# HIVE_BOARD_MISC.net
KiCad netlist of a schematic drawn in Altium Designer
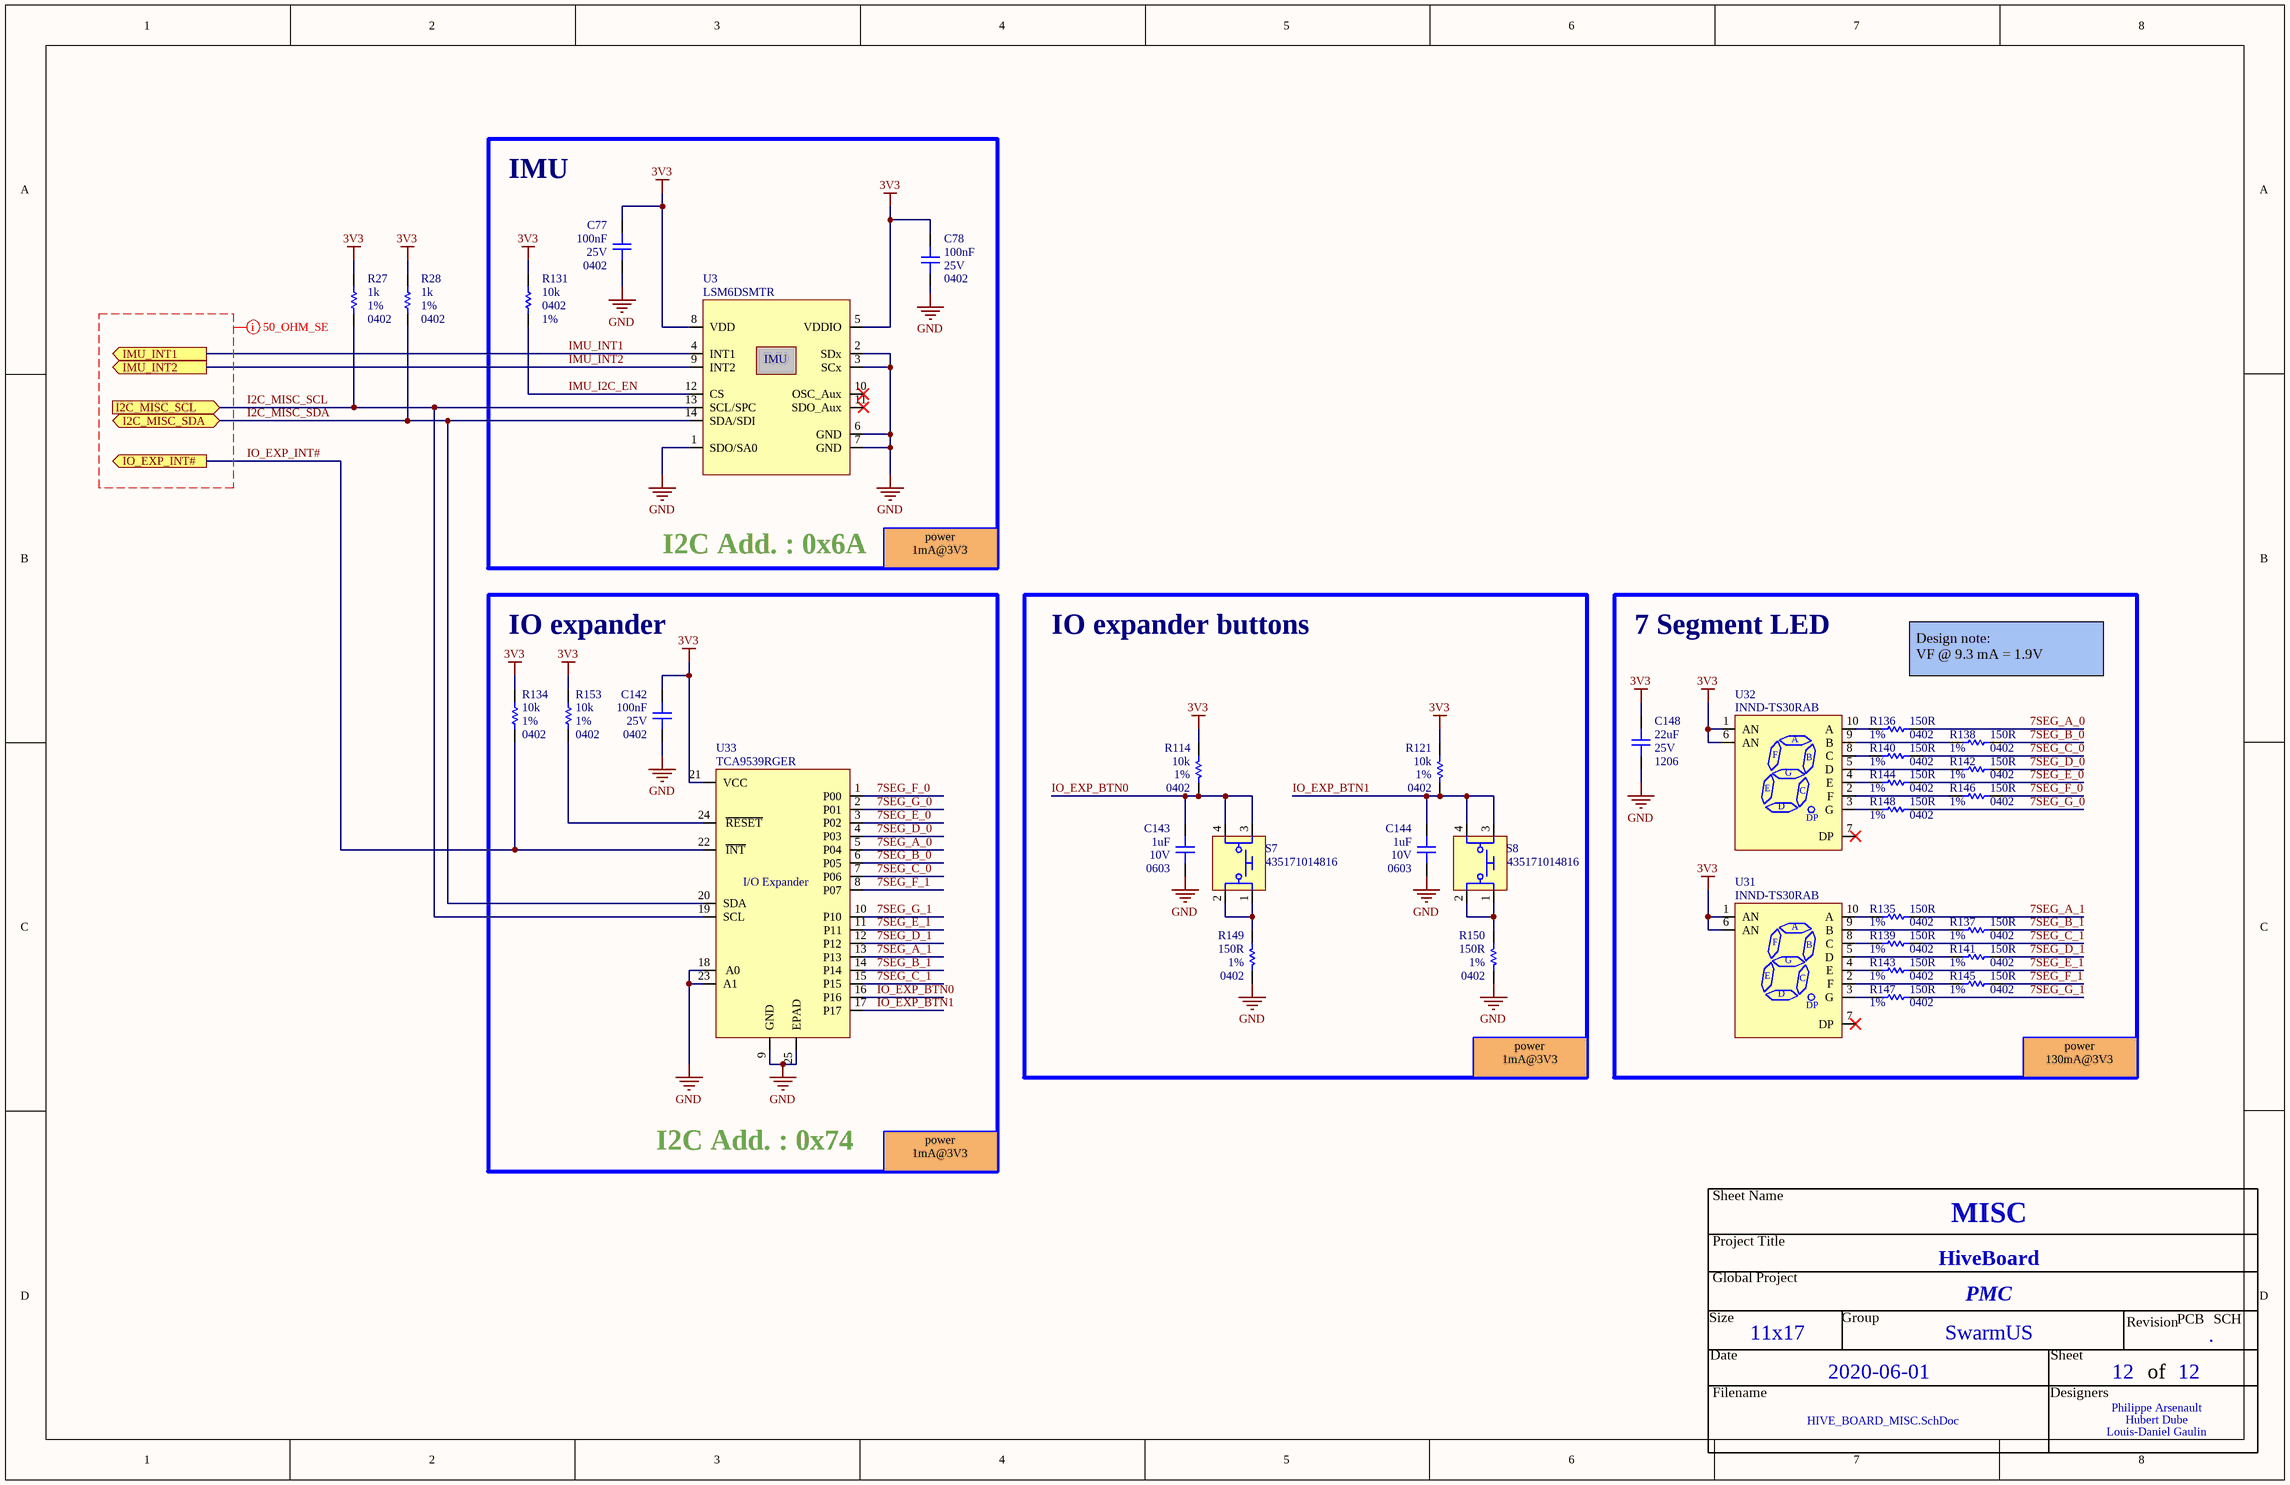
[diagram p0: HIVE_BOARD_MISC.SchDoc]

(export (version "E")
  (design (tool "Eeschema 10.0.6"))
  (components
    (comp (ref "C77")
      (value "100nF")
      (footprint "CAP_CER_0402")
      (description "CAP - CER 0.1µF 10% 25V X7R - 0402")
      (fields
        (field (name "TOLERANCE") "10%")
        (field (name "PACKAGE") "0402")
        (field (name "VOLTAGE RATING") "25V")
        (field (name "Comment") "CGA2B3X7R1E104K050BB")
        (field (name "CREATEDBY/DATE") "Nicolas Roy 2018-11-07")
        (field (name "VERIFIEDBY") "Nicolas V. (2019-01-22)")
      )
      (libsource (lib "GRAMS_MASTER_LIB") (part "CAP_CER_CGA2B3X7R1E104K050BB"))
    )
    (comp (ref "C78")
      (value "100nF")
      (footprint "CAP_CER_0402")
      (description "CAP - CER 0.1µF 10% 25V X7R - 0402")
      (fields
        (field (name "TOLERANCE") "10%")
        (field (name "PACKAGE") "0402")
        (field (name "VOLTAGE RATING") "25V")
        (field (name "Comment") "CGA2B3X7R1E104K050BB")
        (field (name "CREATEDBY/DATE") "Nicolas Roy 2018-11-07")
        (field (name "VERIFIEDBY") "Nicolas V. (2019-01-22)")
      )
      (libsource (lib "GRAMS_MASTER_LIB") (part "CAP_CER_CGA2B3X7R1E104K050BB"))
    )
    (comp (ref "C142")
      (value "100nF")
      (footprint "CAP_CER_0402")
      (description "CAP - CER 0.1µF 10% 25V X7R - 0402")
      (fields
        (field (name "TOLERANCE") "10%")
        (field (name "PACKAGE") "0402")
        (field (name "VOLTAGE RATING") "25V")
        (field (name "Comment") "CGA2B3X7R1E104K050BB")
        (field (name "CREATEDBY/DATE") "Nicolas Roy 2018-11-07")
        (field (name "VERIFIEDBY") "Nicolas V. (2019-01-22)")
      )
      (libsource (lib "GRAMS_MASTER_LIB") (part "CAP_CER_CGA2B3X7R1E104K050BB"))
    )
    (comp (ref "C143")
      (value "1uF")
      (footprint "CAP_CER_0603")
      (description "CAP - CER 1uF 10V 10% X5R - 0603")
      (fields
        (field (name "TOLERANCE") "10%")
        (field (name "PACKAGE") "0603")
        (field (name "VOLTAGE RATING") "10V")
        (field (name "Comment") "C0603C105K8PACTU")
        (field (name "CREATEDBY/DATE") "Hubert Dube - 21/07/20")
        (field (name "VERIFIEDBY") "Louis-Daniel Gaulin - 21/07/20")
      )
      (libsource (lib "SWARMUS_LIB") (part "CAP_CER_C0603C105K8PACTU"))
    )
    (comp (ref "C144")
      (value "1uF")
      (footprint "CAP_CER_0603")
      (description "CAP - CER 1uF 10V 10% X5R - 0603")
      (fields
        (field (name "TOLERANCE") "10%")
        (field (name "PACKAGE") "0603")
        (field (name "VOLTAGE RATING") "10V")
        (field (name "Comment") "C0603C105K8PACTU")
        (field (name "CREATEDBY/DATE") "Hubert Dube - 21/07/20")
        (field (name "VERIFIEDBY") "Louis-Daniel Gaulin - 21/07/20")
      )
      (libsource (lib "SWARMUS_LIB") (part "CAP_CER_C0603C105K8PACTU"))
    )
    (comp (ref "C148")
      (value "22uF")
      (footprint "CAP_CER_1206")
      (description "CAP - CER 22uF 10% 25V X5R - 1206")
      (fields
        (field (name "TOLERANCE") "10%")
        (field (name "PACKAGE") "1206")
        (field (name "VOLTAGE RATING") "25V")
        (field (name "Comment") "CL31A226KAHNNNE")
        (field (name "CREATEDBY/DATE") "Philippe Arsenault/21 Janvier 2020")
        (field (name "VERIFIEDBY") "C.Paulin - 28/01/2020")
      )
      (libsource (lib "GRAMS_MASTER_LIB") (part "CAP_CER_CL31A226KAHNNNE"))
    )
    (comp (ref "R27")
      (value "1k")
      (footprint "RES_0402")
      (description "RES - 1K OHM 1% 1/16W - 0402")
      (fields
        (field (name "TOLERANCE") "1%")
        (field (name "PACKAGE") "0402")
        (field (name "Comment") "RC0402FR-071KL")
        (field (name "CREATEDBY/DATE") "Jonathan Bouchard 2018-07-05")
        (field (name "VERIFIEDBY") "Arnaud Samson 16-07-18")
      )
      (libsource (lib "GRAMS_MASTER_LIB") (part "RES_RC0402FR-071KL"))
    )
    (comp (ref "R28")
      (value "1k")
      (footprint "RES_0402")
      (description "RES - 1K OHM 1% 1/16W - 0402")
      (fields
        (field (name "TOLERANCE") "1%")
        (field (name "PACKAGE") "0402")
        (field (name "Comment") "RC0402FR-071KL")
        (field (name "CREATEDBY/DATE") "Jonathan Bouchard 2018-07-05")
        (field (name "VERIFIEDBY") "Arnaud Samson 16-07-18")
      )
      (libsource (lib "GRAMS_MASTER_LIB") (part "RES_RC0402FR-071KL"))
    )
    (comp (ref "R114")
      (value "10k")
      (footprint "RES_0402")
      (description "RES - 10K OHMS 1% 1/16W - 0402")
      (fields
        (field (name "TOLERANCE") "1%")
        (field (name "PACKAGE") "0402")
        (field (name "Comment") "RC0402FR-0710KL")
        (field (name "CREATEDBY/DATE") "Nicolas V. (2018-11-20)")
        (field (name "VERIFIEDBY") "Nicolas V. (2018-11-20)")
      )
      (libsource (lib "GRAMS_MASTER_LIB") (part "RES_RC0402FR-0710KL"))
    )
    (comp (ref "R121")
      (value "10k")
      (footprint "RES_0402")
      (description "RES - 10K OHMS 1% 1/16W - 0402")
      (fields
        (field (name "TOLERANCE") "1%")
        (field (name "PACKAGE") "0402")
        (field (name "Comment") "RC0402FR-0710KL")
        (field (name "CREATEDBY/DATE") "Nicolas V. (2018-11-20)")
        (field (name "VERIFIEDBY") "Nicolas V. (2018-11-20)")
      )
      (libsource (lib "GRAMS_MASTER_LIB") (part "RES_RC0402FR-0710KL"))
    )
    (comp (ref "R131")
      (value "10k")
      (footprint "RES_0402")
      (description "RES - 10K OHMS 1% 1/16W - 0402")
      (fields
        (field (name "TOLERANCE") "1%")
        (field (name "PACKAGE") "0402")
        (field (name "Comment") "RC0402FR-0710KL")
        (field (name "CREATEDBY/DATE") "Nicolas V. (2018-11-20)")
        (field (name "VERIFIEDBY") "Nicolas V. (2018-11-20)")
      )
      (libsource (lib "GRAMS_MASTER_LIB") (part "RES_RC0402FR-0710KL"))
    )
    (comp (ref "R134")
      (value "10k")
      (footprint "RES_0402")
      (description "RES - 10K OHMS 1% 1/16W - 0402")
      (fields
        (field (name "TOLERANCE") "1%")
        (field (name "PACKAGE") "0402")
        (field (name "Comment") "RC0402FR-0710KL")
        (field (name "CREATEDBY/DATE") "Nicolas V. (2018-11-20)")
        (field (name "VERIFIEDBY") "Nicolas V. (2018-11-20)")
      )
      (libsource (lib "GRAMS_MASTER_LIB") (part "RES_RC0402FR-0710KL"))
    )
    (comp (ref "R135")
      (value "150R")
      (footprint "RES_0402")
      (description "RES - 150R 1% 1/16W - 0402")
      (fields
        (field (name "TOLERANCE") "1%")
        (field (name "PACKAGE") "0402")
        (field (name "Comment") "RC0402FR-07150RL")
        (field (name "CREATEDBY/DATE") "Jonathan Bouchard 2019-03-25")
        (field (name "VERIFIEDBY") "Nicolas V. (2019-05-02)")
      )
      (libsource (lib "GRAMS_MASTER_LIB") (part "RES_RC0402FR-07150RL"))
    )
    (comp (ref "R136")
      (value "150R")
      (footprint "RES_0402")
      (description "RES - 150R 1% 1/16W - 0402")
      (fields
        (field (name "TOLERANCE") "1%")
        (field (name "PACKAGE") "0402")
        (field (name "Comment") "RC0402FR-07150RL")
        (field (name "CREATEDBY/DATE") "Jonathan Bouchard 2019-03-25")
        (field (name "VERIFIEDBY") "Nicolas V. (2019-05-02)")
      )
      (libsource (lib "GRAMS_MASTER_LIB") (part "RES_RC0402FR-07150RL"))
    )
    (comp (ref "R137")
      (value "150R")
      (footprint "RES_0402")
      (description "RES - 150R 1% 1/16W - 0402")
      (fields
        (field (name "TOLERANCE") "1%")
        (field (name "PACKAGE") "0402")
        (field (name "Comment") "RC0402FR-07150RL")
        (field (name "CREATEDBY/DATE") "Jonathan Bouchard 2019-03-25")
        (field (name "VERIFIEDBY") "Nicolas V. (2019-05-02)")
      )
      (libsource (lib "GRAMS_MASTER_LIB") (part "RES_RC0402FR-07150RL"))
    )
    (comp (ref "R138")
      (value "150R")
      (footprint "RES_0402")
      (description "RES - 150R 1% 1/16W - 0402")
      (fields
        (field (name "TOLERANCE") "1%")
        (field (name "PACKAGE") "0402")
        (field (name "Comment") "RC0402FR-07150RL")
        (field (name "CREATEDBY/DATE") "Jonathan Bouchard 2019-03-25")
        (field (name "VERIFIEDBY") "Nicolas V. (2019-05-02)")
      )
      (libsource (lib "GRAMS_MASTER_LIB") (part "RES_RC0402FR-07150RL"))
    )
    (comp (ref "R139")
      (value "150R")
      (footprint "RES_0402")
      (description "RES - 150R 1% 1/16W - 0402")
      (fields
        (field (name "TOLERANCE") "1%")
        (field (name "PACKAGE") "0402")
        (field (name "Comment") "RC0402FR-07150RL")
        (field (name "CREATEDBY/DATE") "Jonathan Bouchard 2019-03-25")
        (field (name "VERIFIEDBY") "Nicolas V. (2019-05-02)")
      )
      (libsource (lib "GRAMS_MASTER_LIB") (part "RES_RC0402FR-07150RL"))
    )
    (comp (ref "R140")
      (value "150R")
      (footprint "RES_0402")
      (description "RES - 150R 1% 1/16W - 0402")
      (fields
        (field (name "TOLERANCE") "1%")
        (field (name "PACKAGE") "0402")
        (field (name "Comment") "RC0402FR-07150RL")
        (field (name "CREATEDBY/DATE") "Jonathan Bouchard 2019-03-25")
        (field (name "VERIFIEDBY") "Nicolas V. (2019-05-02)")
      )
      (libsource (lib "GRAMS_MASTER_LIB") (part "RES_RC0402FR-07150RL"))
    )
    (comp (ref "R141")
      (value "150R")
      (footprint "RES_0402")
      (description "RES - 150R 1% 1/16W - 0402")
      (fields
        (field (name "TOLERANCE") "1%")
        (field (name "PACKAGE") "0402")
        (field (name "Comment") "RC0402FR-07150RL")
        (field (name "CREATEDBY/DATE") "Jonathan Bouchard 2019-03-25")
        (field (name "VERIFIEDBY") "Nicolas V. (2019-05-02)")
      )
      (libsource (lib "GRAMS_MASTER_LIB") (part "RES_RC0402FR-07150RL"))
    )
    (comp (ref "R142")
      (value "150R")
      (footprint "RES_0402")
      (description "RES - 150R 1% 1/16W - 0402")
      (fields
        (field (name "TOLERANCE") "1%")
        (field (name "PACKAGE") "0402")
        (field (name "Comment") "RC0402FR-07150RL")
        (field (name "CREATEDBY/DATE") "Jonathan Bouchard 2019-03-25")
        (field (name "VERIFIEDBY") "Nicolas V. (2019-05-02)")
      )
      (libsource (lib "GRAMS_MASTER_LIB") (part "RES_RC0402FR-07150RL"))
    )
    (comp (ref "R143")
      (value "150R")
      (footprint "RES_0402")
      (description "RES - 150R 1% 1/16W - 0402")
      (fields
        (field (name "TOLERANCE") "1%")
        (field (name "PACKAGE") "0402")
        (field (name "Comment") "RC0402FR-07150RL")
        (field (name "CREATEDBY/DATE") "Jonathan Bouchard 2019-03-25")
        (field (name "VERIFIEDBY") "Nicolas V. (2019-05-02)")
      )
      (libsource (lib "GRAMS_MASTER_LIB") (part "RES_RC0402FR-07150RL"))
    )
    (comp (ref "R144")
      (value "150R")
      (footprint "RES_0402")
      (description "RES - 150R 1% 1/16W - 0402")
      (fields
        (field (name "TOLERANCE") "1%")
        (field (name "PACKAGE") "0402")
        (field (name "Comment") "RC0402FR-07150RL")
        (field (name "CREATEDBY/DATE") "Jonathan Bouchard 2019-03-25")
        (field (name "VERIFIEDBY") "Nicolas V. (2019-05-02)")
      )
      (libsource (lib "GRAMS_MASTER_LIB") (part "RES_RC0402FR-07150RL"))
    )
    (comp (ref "R145")
      (value "150R")
      (footprint "RES_0402")
      (description "RES - 150R 1% 1/16W - 0402")
      (fields
        (field (name "TOLERANCE") "1%")
        (field (name "PACKAGE") "0402")
        (field (name "Comment") "RC0402FR-07150RL")
        (field (name "CREATEDBY/DATE") "Jonathan Bouchard 2019-03-25")
        (field (name "VERIFIEDBY") "Nicolas V. (2019-05-02)")
      )
      (libsource (lib "GRAMS_MASTER_LIB") (part "RES_RC0402FR-07150RL"))
    )
    (comp (ref "R146")
      (value "150R")
      (footprint "RES_0402")
      (description "RES - 150R 1% 1/16W - 0402")
      (fields
        (field (name "TOLERANCE") "1%")
        (field (name "PACKAGE") "0402")
        (field (name "Comment") "RC0402FR-07150RL")
        (field (name "CREATEDBY/DATE") "Jonathan Bouchard 2019-03-25")
        (field (name "VERIFIEDBY") "Nicolas V. (2019-05-02)")
      )
      (libsource (lib "GRAMS_MASTER_LIB") (part "RES_RC0402FR-07150RL"))
    )
    (comp (ref "R147")
      (value "150R")
      (footprint "RES_0402")
      (description "RES - 150R 1% 1/16W - 0402")
      (fields
        (field (name "TOLERANCE") "1%")
        (field (name "PACKAGE") "0402")
        (field (name "Comment") "RC0402FR-07150RL")
        (field (name "CREATEDBY/DATE") "Jonathan Bouchard 2019-03-25")
        (field (name "VERIFIEDBY") "Nicolas V. (2019-05-02)")
      )
      (libsource (lib "GRAMS_MASTER_LIB") (part "RES_RC0402FR-07150RL"))
    )
    (comp (ref "R148")
      (value "150R")
      (footprint "RES_0402")
      (description "RES - 150R 1% 1/16W - 0402")
      (fields
        (field (name "TOLERANCE") "1%")
        (field (name "PACKAGE") "0402")
        (field (name "Comment") "RC0402FR-07150RL")
        (field (name "CREATEDBY/DATE") "Jonathan Bouchard 2019-03-25")
        (field (name "VERIFIEDBY") "Nicolas V. (2019-05-02)")
      )
      (libsource (lib "GRAMS_MASTER_LIB") (part "RES_RC0402FR-07150RL"))
    )
    (comp (ref "R149")
      (value "150R")
      (footprint "RES_0402")
      (description "RES - 150R 1% 1/16W - 0402")
      (fields
        (field (name "TOLERANCE") "1%")
        (field (name "PACKAGE") "0402")
        (field (name "Comment") "RC0402FR-07150RL")
        (field (name "CREATEDBY/DATE") "Jonathan Bouchard 2019-03-25")
        (field (name "VERIFIEDBY") "Nicolas V. (2019-05-02)")
      )
      (libsource (lib "GRAMS_MASTER_LIB") (part "RES_RC0402FR-07150RL"))
    )
    (comp (ref "R150")
      (value "150R")
      (footprint "RES_0402")
      (description "RES - 150R 1% 1/16W - 0402")
      (fields
        (field (name "TOLERANCE") "1%")
        (field (name "PACKAGE") "0402")
        (field (name "Comment") "RC0402FR-07150RL")
        (field (name "CREATEDBY/DATE") "Jonathan Bouchard 2019-03-25")
        (field (name "VERIFIEDBY") "Nicolas V. (2019-05-02)")
      )
      (libsource (lib "GRAMS_MASTER_LIB") (part "RES_RC0402FR-07150RL"))
    )
    (comp (ref "R153")
      (value "10k")
      (footprint "RES_0402")
      (description "RES - 10K OHMS 1% 1/16W - 0402")
      (fields
        (field (name "TOLERANCE") "1%")
        (field (name "PACKAGE") "0402")
        (field (name "Comment") "RC0402FR-0710KL")
        (field (name "CREATEDBY/DATE") "Nicolas V. (2018-11-20)")
        (field (name "VERIFIEDBY") "Nicolas V. (2018-11-20)")
      )
      (libsource (lib "GRAMS_MASTER_LIB") (part "RES_RC0402FR-0710KL"))
    )
    (comp (ref "S7")
      (value "435171014816")
      (footprint "SWI_TACT_435171014816")
      (description "SWI - SWITCH TACTILE SPST-NO 0.05A 12V -SMD")
      (fields
        (field (name "CREATEDBY/DATE") "Hubert Dube - 22/07/20")
        (field (name "VERIFIEDBY") "Louis-Daniel Gaulin / 12-11-2020")
      )
      (libsource (lib "SWARMUS_LIB") (part "SWI_TACT_435171014816"))
    )
    (comp (ref "S8")
      (value "435171014816")
      (footprint "SWI_TACT_435171014816")
      (description "SWI - SWITCH TACTILE SPST-NO 0.05A 12V -SMD")
      (fields
        (field (name "CREATEDBY/DATE") "Hubert Dube - 22/07/20")
        (field (name "VERIFIEDBY") "Louis-Daniel Gaulin / 12-11-2020")
      )
      (libsource (lib "SWARMUS_LIB") (part "SWI_TACT_435171014816"))
    )
    (comp (ref "U3")
      (value "LSM6DSMTR")
      (footprint "SEN_IMU_LSM6DSMTR")
      (description "SEN_IMU -  ACCEL/GYRO 6 Axis I2C/SPI - 14-VFLGA")
      (fields
        (field (name "CREATEDBY/DATE") "Louis-Daniel Gaulin / 06-10-2020")
        (field (name "VERIFIEDBY") "Philippe Arsenault/2020-11-06")
      )
      (libsource (lib "SWARMUS_LIB") (part "SEN_IMU_LSM6DSMTR"))
    )
    (comp (ref "U31")
      (value "INND-TS30RAB")
      (footprint "LED_7SEG_INND-TS30RAB")
      (description "LED_7SEG  - LED Character and Numeric Red 7-Segment 1 Character Common Anode 2V - 10-TH")
      (fields
        (field (name "CREATEDBY/DATE") "Louis-Daniel Gaulin / 10-05-2021")
        (field (name "VERIFIEDBY") "Philippe Arsenault/10-05-2021")
      )
      (libsource (lib "SWARMUS_LIB") (part "LED_7SEG_INND-TS30RAB"))
    )
    (comp (ref "U32")
      (value "INND-TS30RAB")
      (footprint "LED_7SEG_INND-TS30RAB")
      (description "LED_7SEG  - LED Character and Numeric Red 7-Segment 1 Character Common Anode 2V - 10-TH")
      (fields
        (field (name "CREATEDBY/DATE") "Louis-Daniel Gaulin / 10-05-2021")
        (field (name "VERIFIEDBY") "Philippe Arsenault/10-05-2021")
      )
      (libsource (lib "SWARMUS_LIB") (part "LED_7SEG_INND-TS30RAB"))
    )
    (comp (ref "U33")
      (value "TCA9539RGER")
      (footprint "LOG_IOEXP_TCA9539RGER")
      (description "LOG - 16-Bit I2C/SMBus, I/O Expander - 24-VQFN-EP")
      (fields
        (field (name "CREATEDBY/DATE") "Louis-Daniel Gaulin / 10-05-2021")
        (field (name "VERIFIEDBY") "Philippe Arsenault/2021-05-10")
      )
      (libsource (lib "SWARMUS_LIB") (part "LOG_IOEXP_TCA9539RGER"))
    )
  )
  (nets
    (net (code "1") (name "/7SEG_A_0") (class "Default")
      (node (ref "R136") (pin "1") (pinfunction "1_1") (pintype "passive"))
      (node (ref "U33") (pin "5") (pinfunction "P04_5") (pintype "passive"))
    )
    (net (code "2") (name "/7SEG_A_1") (class "Default")
      (node (ref "R135") (pin "1") (pinfunction "1_1") (pintype "passive"))
      (node (ref "U33") (pin "13") (pinfunction "P13_13") (pintype "passive"))
    )
    (net (code "3") (name "/7SEG_B_0") (class "Default")
      (node (ref "R138") (pin "1") (pinfunction "1_1") (pintype "passive"))
      (node (ref "U33") (pin "6") (pinfunction "P05_6") (pintype "passive"))
    )
    (net (code "4") (name "/7SEG_B_1") (class "Default")
      (node (ref "R137") (pin "1") (pinfunction "1_1") (pintype "passive"))
      (node (ref "U33") (pin "14") (pinfunction "P14_14") (pintype "passive"))
    )
    (net (code "5") (name "/7SEG_C_0") (class "Default")
      (node (ref "R140") (pin "1") (pinfunction "1_1") (pintype "passive"))
      (node (ref "U33") (pin "7") (pinfunction "P06_7") (pintype "passive"))
    )
    (net (code "6") (name "/7SEG_C_1") (class "Default")
      (node (ref "R139") (pin "1") (pinfunction "1_1") (pintype "passive"))
      (node (ref "U33") (pin "15") (pinfunction "P15_15") (pintype "passive"))
    )
    (net (code "7") (name "/7SEG_D_0") (class "Default")
      (node (ref "R142") (pin "1") (pinfunction "1_1") (pintype "passive"))
      (node (ref "U33") (pin "4") (pinfunction "P03_4") (pintype "passive"))
    )
    (net (code "8") (name "/7SEG_D_1") (class "Default")
      (node (ref "R141") (pin "1") (pinfunction "1_1") (pintype "passive"))
      (node (ref "U33") (pin "12") (pinfunction "P12_12") (pintype "passive"))
    )
    (net (code "9") (name "/7SEG_E_0") (class "Default")
      (node (ref "R144") (pin "1") (pinfunction "1_1") (pintype "passive"))
      (node (ref "U33") (pin "3") (pinfunction "P02_3") (pintype "passive"))
    )
    (net (code "10") (name "/7SEG_E_1") (class "Default")
      (node (ref "R143") (pin "1") (pinfunction "1_1") (pintype "passive"))
      (node (ref "U33") (pin "11") (pinfunction "P11_11") (pintype "passive"))
    )
    (net (code "11") (name "/7SEG_F_0") (class "Default")
      (node (ref "R146") (pin "1") (pinfunction "1_1") (pintype "passive"))
      (node (ref "U33") (pin "1") (pinfunction "P00_1") (pintype "passive"))
    )
    (net (code "12") (name "/7SEG_F_1") (class "Default")
      (node (ref "R145") (pin "1") (pinfunction "1_1") (pintype "passive"))
      (node (ref "U33") (pin "8") (pinfunction "P07_8") (pintype "passive"))
    )
    (net (code "13") (name "/7SEG_G_0") (class "Default")
      (node (ref "R148") (pin "1") (pinfunction "1_1") (pintype "passive"))
      (node (ref "U33") (pin "2") (pinfunction "P01_2") (pintype "passive"))
    )
    (net (code "14") (name "/7SEG_G_1") (class "Default")
      (node (ref "R147") (pin "1") (pinfunction "1_1") (pintype "passive"))
      (node (ref "U33") (pin "10") (pinfunction "P10_10") (pintype "passive"))
    )
    (net (code "15") (name "/I2C_MISC_SCL") (class "Default")
      (node (ref "R27") (pin "2") (pinfunction "2_2") (pintype "passive"))
      (node (ref "U3") (pin "13") (pinfunction "SCL/SPC_13") (pintype "passive"))
      (node (ref "U33") (pin "19") (pinfunction "SCL_19") (pintype "passive"))
    )
    (net (code "16") (name "/I2C_MISC_SDA") (class "Default")
      (node (ref "R28") (pin "2") (pinfunction "2_2") (pintype "passive"))
      (node (ref "U3") (pin "14") (pinfunction "SDA/SDI_14") (pintype "passive"))
      (node (ref "U33") (pin "20") (pinfunction "SDA_20") (pintype "passive"))
    )
    (net (code "17") (name "/IMU_I2C_EN") (class "Default")
      (node (ref "R131") (pin "2") (pinfunction "2_2") (pintype "passive"))
      (node (ref "U3") (pin "12") (pinfunction "CS_12") (pintype "passive"))
    )
    (net (code "18") (name "/IMU_INT1") (class "Default")
      (node (ref "U3") (pin "4") (pinfunction "INT1_4") (pintype "passive"))
    )
    (net (code "19") (name "/IMU_INT2") (class "Default")
      (node (ref "U3") (pin "9") (pinfunction "INT2_9") (pintype "passive"))
    )
    (net (code "20") (name "/IO_EXP_BTN0") (class "Default")
      (node (ref "C143") (pin "1") (pinfunction "1_1") (pintype "passive"))
      (node (ref "R114") (pin "1") (pinfunction "1_1") (pintype "passive"))
      (node (ref "S7") (pin "3") (pinfunction "3_3") (pintype "passive"))
      (node (ref "S7") (pin "4") (pinfunction "4_4") (pintype "passive"))
      (node (ref "U33") (pin "16") (pinfunction "P16_16") (pintype "passive"))
    )
    (net (code "21") (name "/IO_EXP_BTN1") (class "Default")
      (node (ref "C144") (pin "1") (pinfunction "1_1") (pintype "passive"))
      (node (ref "R121") (pin "1") (pinfunction "1_1") (pintype "passive"))
      (node (ref "S8") (pin "3") (pinfunction "3_3") (pintype "passive"))
      (node (ref "S8") (pin "4") (pinfunction "4_4") (pintype "passive"))
      (node (ref "U33") (pin "17") (pinfunction "P17_17") (pintype "passive"))
    )
    (net (code "22") (name "/IO_EXP_INT#") (class "Default")
      (node (ref "R134") (pin "1") (pinfunction "1_1") (pintype "passive"))
      (node (ref "U33") (pin "22") (pinfunction "INT_22") (pintype "passive"))
    )
    (net (code "23") (name "3V3") (class "Default")
      (node (ref "C142") (pin "1") (pinfunction "1_1") (pintype "passive"))
      (node (ref "C148") (pin "2") (pinfunction "2_2") (pintype "passive"))
      (node (ref "C77") (pin "1") (pinfunction "1_1") (pintype "passive"))
      (node (ref "C78") (pin "1") (pinfunction "1_1") (pintype "passive"))
      (node (ref "R114") (pin "2") (pinfunction "2_2") (pintype "passive"))
      (node (ref "R121") (pin "2") (pinfunction "2_2") (pintype "passive"))
      (node (ref "R131") (pin "1") (pinfunction "1_1") (pintype "passive"))
      (node (ref "R134") (pin "2") (pinfunction "2_2") (pintype "passive"))
      (node (ref "R153") (pin "2") (pinfunction "2_2") (pintype "passive"))
      (node (ref "R27") (pin "1") (pinfunction "1_1") (pintype "passive"))
      (node (ref "R28") (pin "1") (pinfunction "1_1") (pintype "passive"))
      (node (ref "U3") (pin "5") (pinfunction "VDDIO_5") (pintype "passive"))
      (node (ref "U3") (pin "8") (pinfunction "VDD_8") (pintype "passive"))
      (node (ref "U31") (pin "1") (pinfunction "AN_1") (pintype "passive"))
      (node (ref "U31") (pin "6") (pinfunction "AN_6") (pintype "passive"))
      (node (ref "U32") (pin "1") (pinfunction "AN_1") (pintype "passive"))
      (node (ref "U32") (pin "6") (pinfunction "AN_6") (pintype "passive"))
      (node (ref "U33") (pin "21") (pinfunction "VCC_21") (pintype "passive"))
    )
    (net (code "24") (name "GND") (class "Default")
      (node (ref "C142") (pin "2") (pinfunction "2_2") (pintype "passive"))
      (node (ref "C143") (pin "2") (pinfunction "2_2") (pintype "passive"))
      (node (ref "C144") (pin "2") (pinfunction "2_2") (pintype "passive"))
      (node (ref "C148") (pin "1") (pinfunction "1_1") (pintype "passive"))
      (node (ref "C77") (pin "2") (pinfunction "2_2") (pintype "passive"))
      (node (ref "C78") (pin "2") (pinfunction "2_2") (pintype "passive"))
      (node (ref "R149") (pin "1") (pinfunction "1_1") (pintype "passive"))
      (node (ref "R150") (pin "1") (pinfunction "1_1") (pintype "passive"))
      (node (ref "U3") (pin "1") (pinfunction "SDO/SA0_1") (pintype "passive"))
      (node (ref "U3") (pin "2") (pinfunction "SDx_2") (pintype "passive"))
      (node (ref "U3") (pin "3") (pinfunction "SCx_3") (pintype "passive"))
      (node (ref "U3") (pin "6") (pinfunction "GND_6") (pintype "passive"))
      (node (ref "U3") (pin "7") (pinfunction "GND_7") (pintype "passive"))
      (node (ref "U33") (pin "18") (pinfunction "A0_18") (pintype "passive"))
      (node (ref "U33") (pin "23") (pinfunction "A1_23") (pintype "passive"))
      (node (ref "U33") (pin "25") (pinfunction "EPAD_25") (pintype "passive"))
      (node (ref "U33") (pin "9") (pinfunction "GND_9") (pintype "passive"))
    )
    (net (code "25") (name "Net-(R149-Pad2)") (class "Default")
      (node (ref "R149") (pin "2") (pinfunction "2_2") (pintype "passive"))
      (node (ref "S7") (pin "1") (pinfunction "1_1") (pintype "passive"))
      (node (ref "S7") (pin "2") (pinfunction "2_2") (pintype "passive"))
    )
    (net (code "26") (name "Net-(R150-Pad2)") (class "Default")
      (node (ref "R150") (pin "2") (pinfunction "2_2") (pintype "passive"))
      (node (ref "S8") (pin "1") (pinfunction "1_1") (pintype "passive"))
      (node (ref "S8") (pin "2") (pinfunction "2_2") (pintype "passive"))
    )
    (net (code "27") (name "Net-(U31-A)") (class "Default")
      (node (ref "R135") (pin "2") (pinfunction "2_2") (pintype "passive"))
      (node (ref "U31") (pin "10") (pinfunction "A_10") (pintype "passive"))
    )
    (net (code "28") (name "Net-(U31-B)") (class "Default")
      (node (ref "R137") (pin "2") (pinfunction "2_2") (pintype "passive"))
      (node (ref "U31") (pin "9") (pinfunction "B_9") (pintype "passive"))
    )
    (net (code "29") (name "Net-(U31-C)") (class "Default")
      (node (ref "R139") (pin "2") (pinfunction "2_2") (pintype "passive"))
      (node (ref "U31") (pin "8") (pinfunction "C_8") (pintype "passive"))
    )
    (net (code "30") (name "Net-(U31-D)") (class "Default")
      (node (ref "R141") (pin "2") (pinfunction "2_2") (pintype "passive"))
      (node (ref "U31") (pin "5") (pinfunction "D_5") (pintype "passive"))
    )
    (net (code "31") (name "Net-(U31-E)") (class "Default")
      (node (ref "R143") (pin "2") (pinfunction "2_2") (pintype "passive"))
      (node (ref "U31") (pin "4") (pinfunction "E_4") (pintype "passive"))
    )
    (net (code "32") (name "Net-(U31-F)") (class "Default")
      (node (ref "R145") (pin "2") (pinfunction "2_2") (pintype "passive"))
      (node (ref "U31") (pin "2") (pinfunction "F_2") (pintype "passive"))
    )
    (net (code "33") (name "Net-(U31-G)") (class "Default")
      (node (ref "R147") (pin "2") (pinfunction "2_2") (pintype "passive"))
      (node (ref "U31") (pin "3") (pinfunction "G_3") (pintype "passive"))
    )
    (net (code "34") (name "Net-(U32-A)") (class "Default")
      (node (ref "R136") (pin "2") (pinfunction "2_2") (pintype "passive"))
      (node (ref "U32") (pin "10") (pinfunction "A_10") (pintype "passive"))
    )
    (net (code "35") (name "Net-(U32-B)") (class "Default")
      (node (ref "R138") (pin "2") (pinfunction "2_2") (pintype "passive"))
      (node (ref "U32") (pin "9") (pinfunction "B_9") (pintype "passive"))
    )
    (net (code "36") (name "Net-(U32-C)") (class "Default")
      (node (ref "R140") (pin "2") (pinfunction "2_2") (pintype "passive"))
      (node (ref "U32") (pin "8") (pinfunction "C_8") (pintype "passive"))
    )
    (net (code "37") (name "Net-(U32-D)") (class "Default")
      (node (ref "R142") (pin "2") (pinfunction "2_2") (pintype "passive"))
      (node (ref "U32") (pin "5") (pinfunction "D_5") (pintype "passive"))
    )
    (net (code "38") (name "Net-(U32-E)") (class "Default")
      (node (ref "R144") (pin "2") (pinfunction "2_2") (pintype "passive"))
      (node (ref "U32") (pin "4") (pinfunction "E_4") (pintype "passive"))
    )
    (net (code "39") (name "Net-(U32-F)") (class "Default")
      (node (ref "R146") (pin "2") (pinfunction "2_2") (pintype "passive"))
      (node (ref "U32") (pin "2") (pinfunction "F_2") (pintype "passive"))
    )
    (net (code "40") (name "Net-(U32-G)") (class "Default")
      (node (ref "R148") (pin "2") (pinfunction "2_2") (pintype "passive"))
      (node (ref "U32") (pin "3") (pinfunction "G_3") (pintype "passive"))
    )
    (net (code "41") (name "Net-(U33-RESET)") (class "Default")
      (node (ref "R153") (pin "1") (pinfunction "1_1") (pintype "passive"))
      (node (ref "U33") (pin "24") (pinfunction "RESET_24") (pintype "passive"))
    )
    (net (code "42") (name "unconnected-(U3-OSC_Aux-Pad10)") (class "Default")
      (node (ref "U3") (pin "10") (pinfunction "OSC_Aux_10") (pintype "passive+no_connect"))
    )
    (net (code "43") (name "unconnected-(U3-SDO_Aux-Pad11)") (class "Default")
      (node (ref "U3") (pin "11") (pinfunction "SDO_Aux_11") (pintype "passive+no_connect"))
    )
    (net (code "44") (name "unconnected-(U31-DP-Pad7)") (class "Default")
      (node (ref "U31") (pin "7") (pinfunction "DP_7") (pintype "passive+no_connect"))
    )
    (net (code "45") (name "unconnected-(U32-DP-Pad7)") (class "Default")
      (node (ref "U32") (pin "7") (pinfunction "DP_7") (pintype "passive+no_connect"))
    )
  )
)
